# MN_RFID.net
KiCad netlist of a schematic drawn in EAGLE
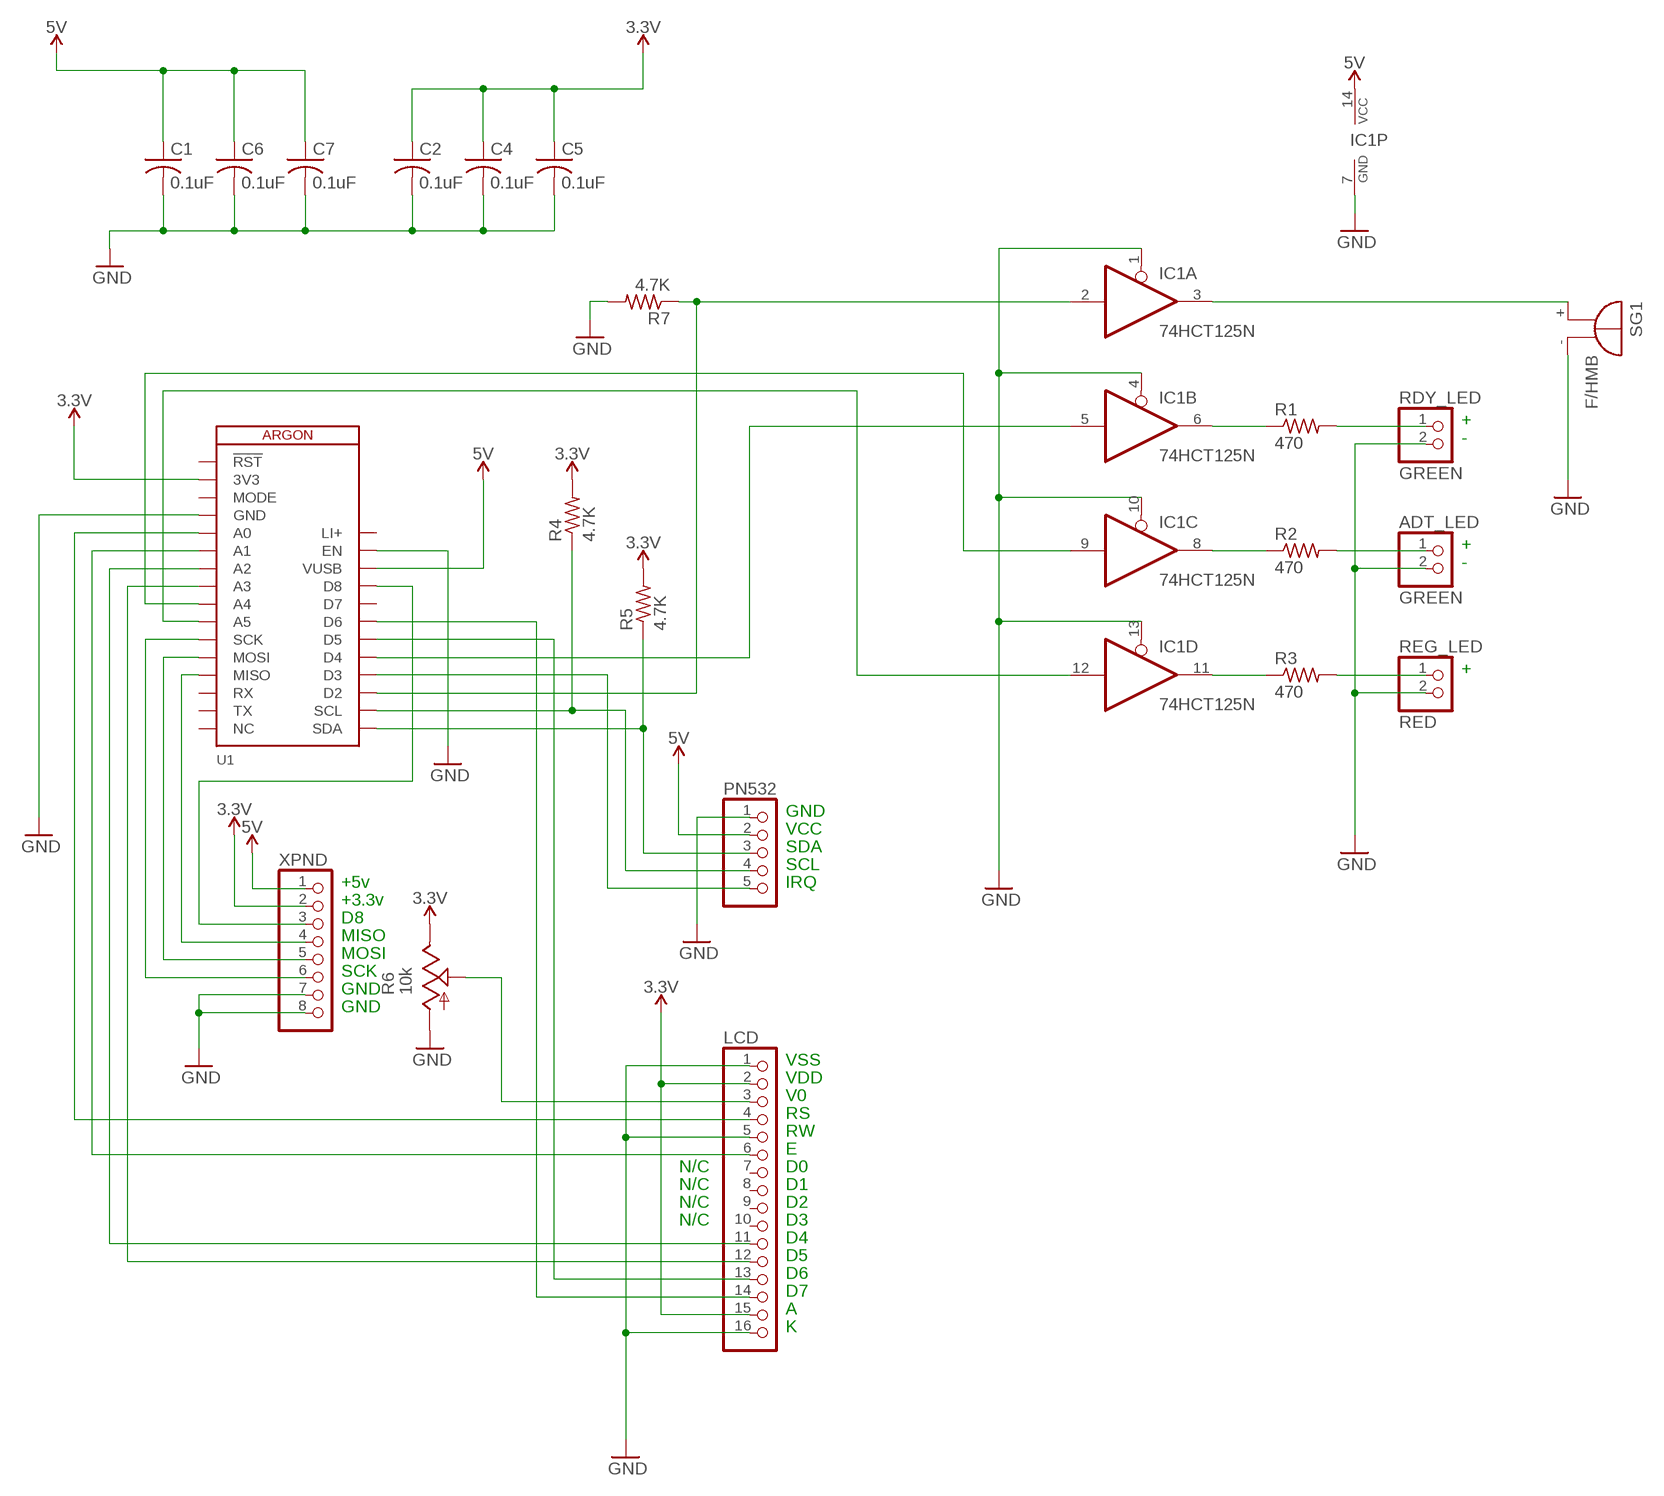
[diagram p0: schematic, sheet 1]

(export (version "E")
  (design (tool "Eeschema 10.0.6"))
  (components
    (comp (ref "ADT_LED")
      (value "GREEN")
      (footprint "eagle-import:1X02")
      (libsource (lib "eagle-import") (part "PINHD-1X2"))
    )
    (comp (ref "C1")
      (value "0.1uF")
      (footprint "eagle-import:C025-024X044")
      (libsource (lib "eagle-import") (part "C-US025-024X044"))
    )
    (comp (ref "C2")
      (value "0.1uF")
      (footprint "eagle-import:C025-024X044")
      (libsource (lib "eagle-import") (part "C-US025-024X044"))
    )
    (comp (ref "C4")
      (value "0.1uF")
      (footprint "eagle-import:C025-024X044")
      (libsource (lib "eagle-import") (part "C-US025-024X044"))
    )
    (comp (ref "C5")
      (value "0.1uF")
      (footprint "eagle-import:C025-024X044")
      (libsource (lib "eagle-import") (part "C-US025-024X044"))
    )
    (comp (ref "C6")
      (value "0.1uF")
      (footprint "eagle-import:C025-024X044")
      (libsource (lib "eagle-import") (part "C-US025-024X044"))
    )
    (comp (ref "C7")
      (value "0.1uF")
      (footprint "eagle-import:C025-024X044")
      (libsource (lib "eagle-import") (part "C-US025-024X044"))
    )
    (comp (ref "IC1")
      (value "74HCT125N")
      (footprint "eagle-import:DIL14")
      (libsource (lib "eagle-import") (part "74125NHCT"))
    )
    (comp (ref "LCD")
      (value "PINHD-1X16")
      (footprint "eagle-import:1X16")
      (libsource (lib "eagle-import") (part "PINHD-1X16"))
    )
    (comp (ref "PN532")
      (value "PINHD-1X5")
      (footprint "eagle-import:1X05")
      (libsource (lib "eagle-import") (part "PINHD-1X5"))
    )
    (comp (ref "R1")
      (value "470")
      (footprint "eagle-import:0204_7")
      (libsource (lib "eagle-import") (part "R-US_0204/7"))
    )
    (comp (ref "R2")
      (value "470")
      (footprint "eagle-import:0204_7")
      (libsource (lib "eagle-import") (part "R-US_0204/7"))
    )
    (comp (ref "R3")
      (value "470")
      (footprint "eagle-import:0204_7")
      (libsource (lib "eagle-import") (part "R-US_0204/7"))
    )
    (comp (ref "R4")
      (value "4.7K")
      (footprint "eagle-import:0204_7")
      (libsource (lib "eagle-import") (part "R-US_0204/7"))
    )
    (comp (ref "R5")
      (value "4.7K")
      (footprint "eagle-import:0204_7")
      (libsource (lib "eagle-import") (part "R-US_0204/7"))
    )
    (comp (ref "R6")
      (value "10k")
      (footprint "eagle-import:CT6")
      (libsource (lib "eagle-import") (part "TRIM_US-CT6"))
    )
    (comp (ref "R7")
      (value "4.7K")
      (footprint "eagle-import:0204_7")
      (libsource (lib "eagle-import") (part "R-US_0204/7"))
    )
    (comp (ref "RDY_LED")
      (value "GREEN")
      (footprint "eagle-import:1X02")
      (libsource (lib "eagle-import") (part "PINHD-1X2"))
    )
    (comp (ref "REG_LED")
      (value "RED")
      (footprint "eagle-import:1X02")
      (libsource (lib "eagle-import") (part "PINHD-1X2"))
    )
    (comp (ref "SG1")
      (value "F/HMB")
      (footprint "eagle-import:F_HMB")
      (libsource (lib "eagle-import") (part "F/HMB"))
    )
    (comp (ref "U1")
      (value "ARGON")
      (footprint "eagle-import:ARGON")
      (libsource (lib "eagle-import") (part "ARGON"))
    )
    (comp (ref "XPND")
      (value "PINHD-1X8BIG")
      (footprint "eagle-import:1X08-BIG")
      (libsource (lib "eagle-import") (part "PINHD-1X8BIG"))
    )
  )
  (nets
    (net (code "1") (name "/LI+") (class "Default")
      (node (ref "U1") (pin "28") (pinfunction "LI+_28") (pintype "power_in"))
    )
    (net (code "2") (name "3.3V") (class "Default")
      (node (ref "C2") (pin "1") (pinfunction "1_1") (pintype "passive"))
      (node (ref "C4") (pin "1") (pinfunction "1_1") (pintype "passive"))
      (node (ref "C5") (pin "1") (pinfunction "1_1") (pintype "passive"))
      (node (ref "LCD") (pin "15") (pinfunction "15_15") (pintype "passive"))
      (node (ref "LCD") (pin "2") (pinfunction "2_2") (pintype "passive"))
      (node (ref "R4") (pin "2") (pinfunction "2_2") (pintype "passive"))
      (node (ref "R5") (pin "2") (pinfunction "2_2") (pintype "passive"))
      (node (ref "R6") (pin "E") (pinfunction "E_E") (pintype "passive"))
      (node (ref "U1") (pin "2") (pinfunction "3V3_2") (pintype "power_in"))
      (node (ref "XPND") (pin "2") (pinfunction "2_2") (pintype "passive"))
    )
    (net (code "3") (name "5V") (class "Default")
      (node (ref "C1") (pin "1") (pinfunction "1_1") (pintype "passive"))
      (node (ref "C6") (pin "1") (pinfunction "1_1") (pintype "passive"))
      (node (ref "C7") (pin "1") (pinfunction "1_1") (pintype "passive"))
      (node (ref "IC1") (pin "14") (pinfunction "VCC_14") (pintype "power_in"))
      (node (ref "PN532") (pin "2") (pinfunction "2_2") (pintype "passive"))
      (node (ref "U1") (pin "26") (pinfunction "VUSB_26") (pintype "power_in"))
      (node (ref "XPND") (pin "1") (pinfunction "1_1") (pintype "passive"))
    )
    (net (code "4") (name "GND") (class "Default")
      (node (ref "ADT_LED") (pin "2") (pinfunction "2_2") (pintype "passive"))
      (node (ref "C1") (pin "2") (pinfunction "2_2") (pintype "passive"))
      (node (ref "C2") (pin "2") (pinfunction "2_2") (pintype "passive"))
      (node (ref "C4") (pin "2") (pinfunction "2_2") (pintype "passive"))
      (node (ref "C5") (pin "2") (pinfunction "2_2") (pintype "passive"))
      (node (ref "C6") (pin "2") (pinfunction "2_2") (pintype "passive"))
      (node (ref "C7") (pin "2") (pinfunction "2_2") (pintype "passive"))
      (node (ref "IC1") (pin "1") (pinfunction "OE_1") (pintype "input"))
      (node (ref "IC1") (pin "10") (pinfunction "OE_10") (pintype "input"))
      (node (ref "IC1") (pin "13") (pinfunction "OE_13") (pintype "input"))
      (node (ref "IC1") (pin "4") (pinfunction "OE_4") (pintype "input"))
      (node (ref "IC1") (pin "7") (pinfunction "GND_7") (pintype "power_in"))
      (node (ref "LCD") (pin "1") (pinfunction "1_1") (pintype "passive"))
      (node (ref "LCD") (pin "16") (pinfunction "16_16") (pintype "passive"))
      (node (ref "LCD") (pin "5") (pinfunction "5_5") (pintype "passive"))
      (node (ref "PN532") (pin "1") (pinfunction "1_1") (pintype "passive"))
      (node (ref "R6") (pin "A") (pinfunction "A_A") (pintype "passive"))
      (node (ref "R7") (pin "2") (pinfunction "2_2") (pintype "passive"))
      (node (ref "RDY_LED") (pin "2") (pinfunction "2_2") (pintype "passive"))
      (node (ref "REG_LED") (pin "2") (pinfunction "2_2") (pintype "passive"))
      (node (ref "SG1") (pin "-") (pinfunction "-_-") (pintype "passive"))
      (node (ref "U1") (pin "27") (pinfunction "EN_27") (pintype "input"))
      (node (ref "U1") (pin "4") (pinfunction "GND_4") (pintype "power_in"))
      (node (ref "XPND") (pin "7") (pinfunction "7_7") (pintype "passive"))
      (node (ref "XPND") (pin "8") (pinfunction "8_8") (pintype "passive"))
    )
    (net (code "5") (name "Net-(ADT_LED-Pad1)") (class "Default")
      (node (ref "ADT_LED") (pin "1") (pinfunction "1_1") (pintype "passive"))
      (node (ref "R2") (pin "2") (pinfunction "2_2") (pintype "passive"))
    )
    (net (code "6") (name "Net-(IC1A-I)") (class "Default")
      (node (ref "IC1") (pin "2") (pinfunction "I_2") (pintype "input"))
      (node (ref "R7") (pin "1") (pinfunction "1_1") (pintype "passive"))
      (node (ref "U1") (pin "19") (pinfunction "D2_19") (pintype "bidirectional"))
    )
    (net (code "7") (name "Net-(IC1A-O)") (class "Default")
      (node (ref "IC1") (pin "3") (pinfunction "O_3") (pintype "tri_state"))
      (node (ref "SG1") (pin "+") (pinfunction "+_+") (pintype "passive"))
    )
    (net (code "8") (name "Net-(IC1B-I)") (class "Default")
      (node (ref "IC1") (pin "5") (pinfunction "I_5") (pintype "input"))
      (node (ref "U1") (pin "21") (pinfunction "D4_21") (pintype "bidirectional"))
    )
    (net (code "9") (name "Net-(IC1B-O)") (class "Default")
      (node (ref "IC1") (pin "6") (pinfunction "O_6") (pintype "tri_state"))
      (node (ref "R1") (pin "1") (pinfunction "1_1") (pintype "passive"))
    )
    (net (code "10") (name "Net-(IC1C-I)") (class "Default")
      (node (ref "IC1") (pin "9") (pinfunction "I_9") (pintype "input"))
      (node (ref "U1") (pin "9") (pinfunction "A4_9") (pintype "bidirectional"))
    )
    (net (code "11") (name "Net-(IC1C-O)") (class "Default")
      (node (ref "IC1") (pin "8") (pinfunction "O_8") (pintype "tri_state"))
      (node (ref "R2") (pin "1") (pinfunction "1_1") (pintype "passive"))
    )
    (net (code "12") (name "Net-(IC1D-I)") (class "Default")
      (node (ref "IC1") (pin "12") (pinfunction "I_12") (pintype "input"))
      (node (ref "U1") (pin "10") (pinfunction "A5_10") (pintype "bidirectional"))
    )
    (net (code "13") (name "Net-(IC1D-O)") (class "Default")
      (node (ref "IC1") (pin "11") (pinfunction "O_11") (pintype "tri_state"))
      (node (ref "R3") (pin "1") (pinfunction "1_1") (pintype "passive"))
    )
    (net (code "14") (name "Net-(LCD-Pad3)") (class "Default")
      (node (ref "LCD") (pin "3") (pinfunction "3_3") (pintype "passive"))
      (node (ref "R6") (pin "S") (pinfunction "S_S") (pintype "passive"))
    )
    (net (code "15") (name "Net-(R1-Pad2)") (class "Default")
      (node (ref "R1") (pin "2") (pinfunction "2_2") (pintype "passive"))
      (node (ref "RDY_LED") (pin "1") (pinfunction "1_1") (pintype "passive"))
    )
    (net (code "16") (name "Net-(R3-Pad2)") (class "Default")
      (node (ref "R3") (pin "2") (pinfunction "2_2") (pintype "passive"))
      (node (ref "REG_LED") (pin "1") (pinfunction "1_1") (pintype "passive"))
    )
    (net (code "17") (name "Net-(U1-A0)") (class "Default")
      (node (ref "LCD") (pin "4") (pinfunction "4_4") (pintype "passive"))
      (node (ref "U1") (pin "5") (pinfunction "A0_5") (pintype "bidirectional"))
    )
    (net (code "18") (name "Net-(U1-A1)") (class "Default")
      (node (ref "LCD") (pin "6") (pinfunction "6_6") (pintype "passive"))
      (node (ref "U1") (pin "6") (pinfunction "A1_6") (pintype "bidirectional"))
    )
    (net (code "19") (name "Net-(U1-A2)") (class "Default")
      (node (ref "LCD") (pin "11") (pinfunction "11_11") (pintype "passive"))
      (node (ref "U1") (pin "7") (pinfunction "A2_7") (pintype "bidirectional"))
    )
    (net (code "20") (name "Net-(U1-A3)") (class "Default")
      (node (ref "LCD") (pin "12") (pinfunction "12_12") (pintype "passive"))
      (node (ref "U1") (pin "8") (pinfunction "A3_8") (pintype "bidirectional"))
    )
    (net (code "21") (name "Net-(U1-D3)") (class "Default")
      (node (ref "PN532") (pin "5") (pinfunction "5_5") (pintype "passive"))
      (node (ref "U1") (pin "20") (pinfunction "D3_20") (pintype "bidirectional"))
    )
    (net (code "22") (name "Net-(U1-D5)") (class "Default")
      (node (ref "LCD") (pin "13") (pinfunction "13_13") (pintype "passive"))
      (node (ref "U1") (pin "22") (pinfunction "D5_22") (pintype "bidirectional"))
    )
    (net (code "23") (name "Net-(U1-D6)") (class "Default")
      (node (ref "LCD") (pin "14") (pinfunction "14_14") (pintype "passive"))
      (node (ref "U1") (pin "23") (pinfunction "D6_23") (pintype "bidirectional"))
    )
    (net (code "24") (name "Net-(U1-D8)") (class "Default")
      (node (ref "U1") (pin "25") (pinfunction "D8_25") (pintype "bidirectional"))
      (node (ref "XPND") (pin "3") (pinfunction "3_3") (pintype "passive"))
    )
    (net (code "25") (name "Net-(U1-MISO)") (class "Default")
      (node (ref "U1") (pin "13") (pinfunction "MISO_13") (pintype "bidirectional"))
      (node (ref "XPND") (pin "4") (pinfunction "4_4") (pintype "passive"))
    )
    (net (code "26") (name "Net-(U1-MOSI)") (class "Default")
      (node (ref "U1") (pin "12") (pinfunction "MOSI_12") (pintype "bidirectional"))
      (node (ref "XPND") (pin "5") (pinfunction "5_5") (pintype "passive"))
    )
    (net (code "27") (name "Net-(U1-SCK)") (class "Default")
      (node (ref "U1") (pin "11") (pinfunction "SCK_11") (pintype "bidirectional"))
      (node (ref "XPND") (pin "6") (pinfunction "6_6") (pintype "passive"))
    )
    (net (code "28") (name "Net-(U1-SCL)") (class "Default")
      (node (ref "PN532") (pin "4") (pinfunction "4_4") (pintype "passive"))
      (node (ref "R4") (pin "1") (pinfunction "1_1") (pintype "passive"))
      (node (ref "U1") (pin "18") (pinfunction "SCL_18") (pintype "bidirectional"))
    )
    (net (code "29") (name "Net-(U1-SDA)") (class "Default")
      (node (ref "PN532") (pin "3") (pinfunction "3_3") (pintype "passive"))
      (node (ref "R5") (pin "1") (pinfunction "1_1") (pintype "passive"))
      (node (ref "U1") (pin "17") (pinfunction "SDA_17") (pintype "bidirectional"))
    )
    (net (code "30") (name "unconnected-(LCD-Pad7)") (class "Default")
      (node (ref "LCD") (pin "7") (pinfunction "7_7") (pintype "passive"))
    )
    (net (code "31") (name "unconnected-(LCD-Pad8)") (class "Default")
      (node (ref "LCD") (pin "8") (pinfunction "8_8") (pintype "passive"))
    )
    (net (code "32") (name "unconnected-(LCD-Pad9)") (class "Default")
      (node (ref "LCD") (pin "9") (pinfunction "9_9") (pintype "passive"))
    )
    (net (code "33") (name "unconnected-(LCD-Pad10)") (class "Default")
      (node (ref "LCD") (pin "10") (pinfunction "10_10") (pintype "passive"))
    )
    (net (code "34") (name "unconnected-(U1-D7-Pad24)") (class "Default")
      (node (ref "U1") (pin "24") (pinfunction "D7_24") (pintype "bidirectional"))
    )
    (net (code "35") (name "unconnected-(U1-MODE-Pad3)") (class "Default")
      (node (ref "U1") (pin "3") (pinfunction "MODE_3") (pintype "bidirectional"))
    )
    (net (code "36") (name "unconnected-(U1-NC-Pad16)") (class "Default")
      (node (ref "U1") (pin "16") (pinfunction "NC_16") (pintype "bidirectional"))
    )
    (net (code "37") (name "unconnected-(U1-RX-Pad14)") (class "Default")
      (node (ref "U1") (pin "14") (pinfunction "RX_14") (pintype "bidirectional"))
    )
    (net (code "38") (name "unconnected-(U1-TX-Pad15)") (class "Default")
      (node (ref "U1") (pin "15") (pinfunction "TX_15") (pintype "bidirectional"))
    )
    (net (code "39") (name "unconnected-(U1-~{RST}-Pad1)") (class "Default")
      (node (ref "U1") (pin "1") (pinfunction "~{RST}_1") (pintype "input"))
    )
  )
)
